# HB-UNI-SenAct-4-4-RC_V3_0.net
KiCad netlist of a schematic drawn in EAGLE
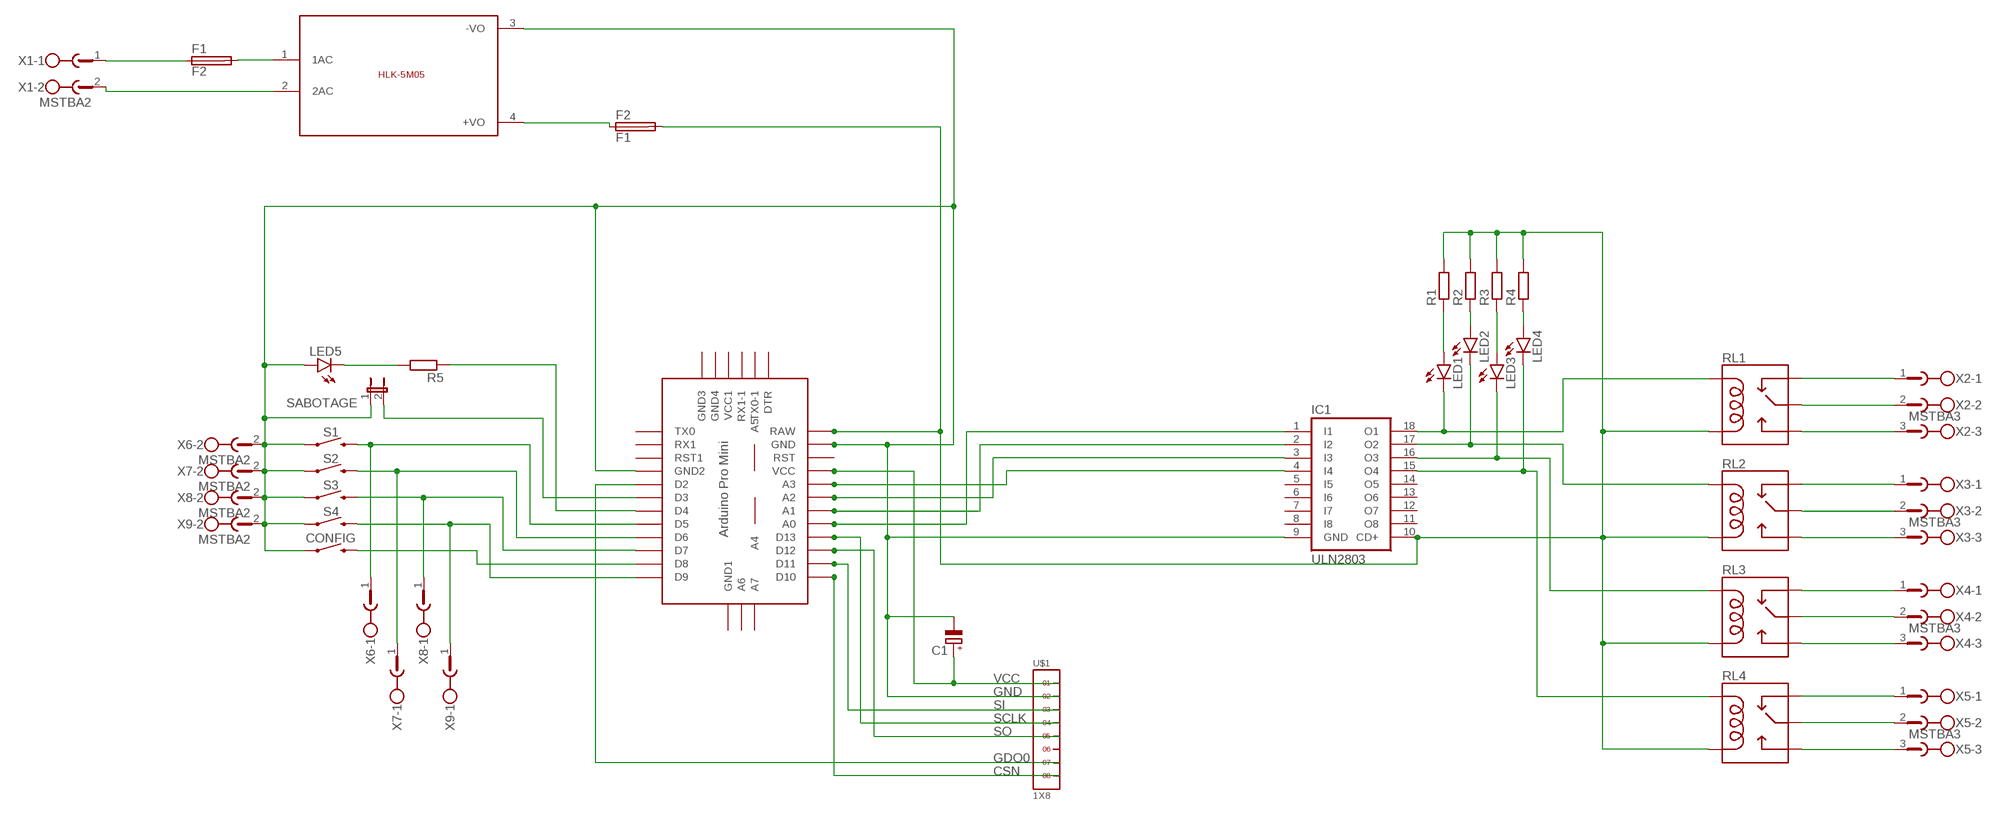
[diagram p0: schematic, sheet 1]

(export (version "E")
  (design (tool "Eeschema 10.0.6"))
  (components
    (comp (ref "C1")
      (value "CPOL-EUE2.5-5")
      (footprint "eagle-import:E2,5-5")
      (libsource (lib "eagle-import") (part "CPOL-EUE2.5-5"))
    )
    (comp (ref "CONFIG")
      (value "MOMENTARY-SWITCH-SPST-PTH-6.0MM-KIT")
      (footprint "eagle-import:TACTILE_SWITCH_PTH_6.0MM_KIT")
      (libsource (lib "eagle-import") (part "MOMENTARY-SWITCH-SPST-PTH-6.0MM-KIT"))
    )
    (comp (ref "F1")
      (value "F2")
      (footprint "eagle-import:SH22,5A")
      (fields (field (name "MPN") "0031.7701.11"))
      (libsource (lib "eagle-import") (part "SH22,5A"))
    )
    (comp (ref "F2")
      (value "F1")
      (footprint "eagle-import:SH22,5A")
      (fields (field (name "MPN") "0031.7701.11"))
      (libsource (lib "eagle-import") (part "SH22,5A"))
    )
    (comp (ref "IC1")
      (value "ULN2803")
      (footprint "eagle-import:DIL18")
      (libsource (lib "eagle-import") (part "ULN2803A"))
    )
    (comp (ref "LED1")
      (value "LED3MM")
      (footprint "eagle-import:LED3MM")
      (libsource (lib "eagle-import") (part "LED3MM"))
    )
    (comp (ref "LED2")
      (value "LED3MM")
      (footprint "eagle-import:LED3MM")
      (libsource (lib "eagle-import") (part "LED3MM"))
    )
    (comp (ref "LED3")
      (value "LED3MM")
      (footprint "eagle-import:LED3MM")
      (libsource (lib "eagle-import") (part "LED3MM"))
    )
    (comp (ref "LED4")
      (value "LED3MM")
      (footprint "eagle-import:LED3MM")
      (libsource (lib "eagle-import") (part "LED3MM"))
    )
    (comp (ref "LED5")
      (value "LED3MM")
      (footprint "eagle-import:LED3MM")
      (libsource (lib "eagle-import") (part "LED3MM"))
    )
    (comp (ref "R1")
      (value "R-EU_0309/10")
      (footprint "eagle-import:0309_10")
      (libsource (lib "eagle-import") (part "R-EU_0309/10"))
    )
    (comp (ref "R2")
      (value "R-EU_0309/10")
      (footprint "eagle-import:0309_10")
      (libsource (lib "eagle-import") (part "R-EU_0309/10"))
    )
    (comp (ref "R3")
      (value "R-EU_0309/10")
      (footprint "eagle-import:0309_10")
      (libsource (lib "eagle-import") (part "R-EU_0309/10"))
    )
    (comp (ref "R4")
      (value "R-EU_0309/10")
      (footprint "eagle-import:0309_10")
      (libsource (lib "eagle-import") (part "R-EU_0309/10"))
    )
    (comp (ref "R5")
      (value "R-EU_0309/10")
      (footprint "eagle-import:0309_10")
      (libsource (lib "eagle-import") (part "R-EU_0309/10"))
    )
    (comp (ref "RL1")
      (value "RELAYPTH")
      (footprint "eagle-import:SRD-05VDC-SL-C")
      (libsource (lib "eagle-import") (part "RELAYPTH"))
    )
    (comp (ref "RL2")
      (value "RL2")
      (footprint "eagle-import:SRD-05VDC-SL-C")
      (libsource (lib "eagle-import") (part "RELAYPTH"))
    )
    (comp (ref "RL3")
      (value "RELAYPTH")
      (footprint "eagle-import:SRD-05VDC-SL-C")
      (libsource (lib "eagle-import") (part "RELAYPTH"))
    )
    (comp (ref "RL4")
      (value "RELAYPTH")
      (footprint "eagle-import:SRD-05VDC-SL-C")
      (libsource (lib "eagle-import") (part "RELAYPTH"))
    )
    (comp (ref "S1")
      (value "MOMENTARY-SWITCH-SPST-PTH-6.0MM")
      (footprint "eagle-import:TACTILE_SWITCH_PTH_6.0MM")
      (libsource (lib "eagle-import") (part "MOMENTARY-SWITCH-SPST-PTH-6.0MM"))
    )
    (comp (ref "S2")
      (value "MOMENTARY-SWITCH-SPST-PTH-6.0MM-KIT")
      (footprint "eagle-import:TACTILE_SWITCH_PTH_6.0MM_KIT")
      (libsource (lib "eagle-import") (part "MOMENTARY-SWITCH-SPST-PTH-6.0MM-KIT"))
    )
    (comp (ref "S3")
      (value "MOMENTARY-SWITCH-SPST-PTH-6.0MM-KIT")
      (footprint "eagle-import:TACTILE_SWITCH_PTH_6.0MM_KIT")
      (libsource (lib "eagle-import") (part "MOMENTARY-SWITCH-SPST-PTH-6.0MM-KIT"))
    )
    (comp (ref "S4")
      (value "MOMENTARY-SWITCH-SPST-PTH-6.0MM-KIT")
      (footprint "eagle-import:TACTILE_SWITCH_PTH_6.0MM_KIT")
      (libsource (lib "eagle-import") (part "MOMENTARY-SWITCH-SPST-PTH-6.0MM-KIT"))
    )
    (comp (ref "SABOTAGE")
      (value "JP1E")
      (footprint "eagle-import:JP1")
      (libsource (lib "eagle-import") (part "JP1E"))
    )
    (comp (ref "U$1")
      (value "1X8")
      (footprint "eagle-import:1X8")
      (libsource (lib "eagle-import") (part "1X8"))
    )
    (comp (ref "U$2")
      (value "ABK-PRO-MINI")
      (footprint "eagle-import:ABK-PRO-MINI")
      (libsource (lib "eagle-import") (part "ABK-PRO-MINI"))
    )
    (comp (ref "U$3")
      (value "5VDC/5W")
      (footprint "eagle-import:HLK-5M05")
      (libsource (lib "eagle-import") (part "HLK-5M05"))
    )
    (comp (ref "X1")
      (value "MSTBA2")
      (footprint "eagle-import:MSTBA2")
      (fields (field (name "MF") "FARNELL") (field (name "MPN") "1757242"))
      (libsource (lib "eagle-import") (part "MSTBA2"))
    )
    (comp (ref "X2")
      (value "MSTBA3")
      (footprint "eagle-import:MSTBA3")
      (fields (field (name "MF") "FARNELL") (field (name "MPN") "1757255"))
      (libsource (lib "eagle-import") (part "MSTBA3"))
    )
    (comp (ref "X3")
      (value "MSTBA3")
      (footprint "eagle-import:MSTBA3")
      (fields (field (name "MF") "FARNELL") (field (name "MPN") "1757255"))
      (libsource (lib "eagle-import") (part "MSTBA3"))
    )
    (comp (ref "X4")
      (value "MSTBA3")
      (footprint "eagle-import:MSTBA3")
      (fields (field (name "MF") "FARNELL") (field (name "MPN") "1757255"))
      (libsource (lib "eagle-import") (part "MSTBA3"))
    )
    (comp (ref "X5")
      (value "MSTBA3")
      (footprint "eagle-import:MSTBA3")
      (fields (field (name "MF") "FARNELL") (field (name "MPN") "1757255"))
      (libsource (lib "eagle-import") (part "MSTBA3"))
    )
    (comp (ref "X6")
      (value "MSTBA2")
      (footprint "eagle-import:MSTBA2")
      (fields (field (name "MF") "FARNELL") (field (name "MPN") "1757242"))
      (libsource (lib "eagle-import") (part "MSTBA2"))
    )
    (comp (ref "X7")
      (value "MSTBA2")
      (footprint "eagle-import:MSTBA2")
      (fields (field (name "MF") "FARNELL") (field (name "MPN") "1757242"))
      (libsource (lib "eagle-import") (part "MSTBA2"))
    )
    (comp (ref "X8")
      (value "MSTBA2")
      (footprint "eagle-import:MSTBA2")
      (fields (field (name "MF") "FARNELL") (field (name "MPN") "1757242"))
      (libsource (lib "eagle-import") (part "MSTBA2"))
    )
    (comp (ref "X9")
      (value "MSTBA2")
      (footprint "eagle-import:MSTBA2")
      (fields (field (name "MF") "FARNELL") (field (name "MPN") "1757242"))
      (libsource (lib "eagle-import") (part "MSTBA2"))
    )
  )
  (nets
    (net (code "1") (name "/CSN") (class "Default")
      (node (ref "U$1") (pin "8") (pinfunction "8_8") (pintype "bidirectional"))
      (node (ref "U$2") (pin "D10") (pinfunction "D10_D10") (pintype "bidirectional"))
    )
    (net (code "2") (name "/GDO0") (class "Default")
      (node (ref "U$1") (pin "7") (pinfunction "7_7") (pintype "bidirectional"))
      (node (ref "U$2") (pin "D2") (pinfunction "D2_D2") (pintype "bidirectional"))
    )
    (net (code "3") (name "/GND") (class "Default")
      (node (ref "C1") (pin "-") (pinfunction "-_-") (pintype "passive"))
      (node (ref "CONFIG") (pin "1") (pinfunction "1_1") (pintype "passive"))
      (node (ref "IC1") (pin "9") (pinfunction "GND_9") (pintype "power_in"))
      (node (ref "LED5") (pin "A") (pinfunction "A_A") (pintype "passive"))
      (node (ref "S1") (pin "1") (pinfunction "1_1") (pintype "passive"))
      (node (ref "S2") (pin "1") (pinfunction "1_1") (pintype "passive"))
      (node (ref "S3") (pin "1") (pinfunction "1_1") (pintype "passive"))
      (node (ref "S4") (pin "1") (pinfunction "1_1") (pintype "passive"))
      (node (ref "SABOTAGE") (pin "1") (pinfunction "1_1") (pintype "passive"))
      (node (ref "U$1") (pin "2") (pinfunction "2_2") (pintype "bidirectional"))
      (node (ref "U$2") (pin "GND") (pinfunction "GND_GND") (pintype "bidirectional"))
      (node (ref "U$2") (pin "GND1") (pinfunction "GND2_GND1") (pintype "bidirectional"))
      (node (ref "U$3") (pin "3") (pinfunction "-VO_3") (pintype "bidirectional"))
      (node (ref "X6") (pin "2") (pinfunction "1_2") (pintype "passive"))
      (node (ref "X7") (pin "2") (pinfunction "1_2") (pintype "passive"))
      (node (ref "X8") (pin "2") (pinfunction "1_2") (pintype "passive"))
      (node (ref "X9") (pin "2") (pinfunction "1_2") (pintype "passive"))
    )
    (net (code "4") (name "/SCLK") (class "Default")
      (node (ref "U$1") (pin "4") (pinfunction "4_4") (pintype "bidirectional"))
      (node (ref "U$2") (pin "D13") (pinfunction "D13_D13") (pintype "bidirectional"))
    )
    (net (code "5") (name "/SI") (class "Default")
      (node (ref "U$1") (pin "3") (pinfunction "3_3") (pintype "bidirectional"))
      (node (ref "U$2") (pin "D11") (pinfunction "D11_D11") (pintype "bidirectional"))
    )
    (net (code "6") (name "/SO") (class "Default")
      (node (ref "U$1") (pin "5") (pinfunction "5_5") (pintype "bidirectional"))
      (node (ref "U$2") (pin "D12") (pinfunction "D12_D12") (pintype "bidirectional"))
    )
    (net (code "7") (name "/VCC") (class "Default")
      (node (ref "C1") (pin "+") (pinfunction "+_+") (pintype "passive"))
      (node (ref "U$1") (pin "1") (pinfunction "1_1") (pintype "bidirectional"))
      (node (ref "U$2") (pin "VCC") (pinfunction "VCC_VCC") (pintype "bidirectional"))
    )
    (net (code "8") (name "Net-(CONFIG-2)") (class "Default")
      (node (ref "CONFIG") (pin "3") (pinfunction "2_3") (pintype "passive"))
      (node (ref "U$2") (pin "D8") (pinfunction "D8_D8") (pintype "bidirectional"))
    )
    (net (code "9") (name "Net-(F1-Pad1)") (class "Default")
      (node (ref "F1") (pin "1") (pinfunction "1_1") (pintype "passive"))
      (node (ref "X1") (pin "1") (pinfunction "1_1") (pintype "passive"))
    )
    (net (code "10") (name "Net-(IC1-CD+)") (class "Default")
      (node (ref "F2") (pin "2") (pinfunction "2_2") (pintype "passive"))
      (node (ref "IC1") (pin "10") (pinfunction "CD+_10") (pintype "passive"))
      (node (ref "R1") (pin "2") (pinfunction "2_2") (pintype "passive"))
      (node (ref "R2") (pin "2") (pinfunction "2_2") (pintype "passive"))
      (node (ref "R3") (pin "2") (pinfunction "2_2") (pintype "passive"))
      (node (ref "R4") (pin "2") (pinfunction "2_2") (pintype "passive"))
      (node (ref "RL1") (pin "COIL0") (pinfunction "COIL0_COIL0") (pintype "bidirectional"))
      (node (ref "RL2") (pin "COIL0") (pinfunction "COIL0_COIL0") (pintype "bidirectional"))
      (node (ref "RL3") (pin "COIL0") (pinfunction "COIL0_COIL0") (pintype "bidirectional"))
      (node (ref "RL4") (pin "COIL0") (pinfunction "COIL0_COIL0") (pintype "bidirectional"))
      (node (ref "U$2") (pin "RAW") (pinfunction "RAW_RAW") (pintype "bidirectional"))
    )
    (net (code "11") (name "Net-(IC1-I1)") (class "Default")
      (node (ref "IC1") (pin "1") (pinfunction "I1_1") (pintype "input"))
      (node (ref "U$2") (pin "A0") (pinfunction "A0_A0") (pintype "bidirectional"))
    )
    (net (code "12") (name "Net-(IC1-I2)") (class "Default")
      (node (ref "IC1") (pin "2") (pinfunction "I2_2") (pintype "input"))
      (node (ref "U$2") (pin "A1") (pinfunction "A1_A1") (pintype "bidirectional"))
    )
    (net (code "13") (name "Net-(IC1-I3)") (class "Default")
      (node (ref "IC1") (pin "3") (pinfunction "I3_3") (pintype "input"))
      (node (ref "U$2") (pin "A2") (pinfunction "A2_A2") (pintype "bidirectional"))
    )
    (net (code "14") (name "Net-(IC1-I4)") (class "Default")
      (node (ref "IC1") (pin "4") (pinfunction "I4_4") (pintype "input"))
      (node (ref "U$2") (pin "A3") (pinfunction "A3_A3") (pintype "bidirectional"))
    )
    (net (code "15") (name "Net-(IC1-O1)") (class "Default")
      (node (ref "IC1") (pin "18") (pinfunction "O1_18") (pintype "open_collector"))
      (node (ref "LED1") (pin "K") (pinfunction "C_K") (pintype "passive"))
      (node (ref "RL1") (pin "COIL1") (pinfunction "COIL1_COIL1") (pintype "bidirectional"))
    )
    (net (code "16") (name "Net-(IC1-O2)") (class "Default")
      (node (ref "IC1") (pin "17") (pinfunction "O2_17") (pintype "open_collector"))
      (node (ref "LED2") (pin "K") (pinfunction "C_K") (pintype "passive"))
      (node (ref "RL2") (pin "COIL1") (pinfunction "COIL1_COIL1") (pintype "bidirectional"))
    )
    (net (code "17") (name "Net-(IC1-O3)") (class "Default")
      (node (ref "IC1") (pin "16") (pinfunction "O3_16") (pintype "open_collector"))
      (node (ref "LED3") (pin "K") (pinfunction "C_K") (pintype "passive"))
      (node (ref "RL3") (pin "COIL1") (pinfunction "COIL1_COIL1") (pintype "bidirectional"))
    )
    (net (code "18") (name "Net-(IC1-O4)") (class "Default")
      (node (ref "IC1") (pin "15") (pinfunction "O4_15") (pintype "open_collector"))
      (node (ref "LED4") (pin "K") (pinfunction "C_K") (pintype "passive"))
      (node (ref "RL4") (pin "COIL1") (pinfunction "COIL1_COIL1") (pintype "bidirectional"))
    )
    (net (code "19") (name "Net-(LED1-PadA)") (class "Default")
      (node (ref "LED1") (pin "A") (pinfunction "A_A") (pintype "passive"))
      (node (ref "R1") (pin "1") (pinfunction "1_1") (pintype "passive"))
    )
    (net (code "20") (name "Net-(LED2-PadA)") (class "Default")
      (node (ref "LED2") (pin "A") (pinfunction "A_A") (pintype "passive"))
      (node (ref "R2") (pin "1") (pinfunction "1_1") (pintype "passive"))
    )
    (net (code "21") (name "Net-(LED3-PadA)") (class "Default")
      (node (ref "LED3") (pin "A") (pinfunction "A_A") (pintype "passive"))
      (node (ref "R3") (pin "1") (pinfunction "1_1") (pintype "passive"))
    )
    (net (code "22") (name "Net-(LED4-PadA)") (class "Default")
      (node (ref "LED4") (pin "A") (pinfunction "A_A") (pintype "passive"))
      (node (ref "R4") (pin "1") (pinfunction "1_1") (pintype "passive"))
    )
    (net (code "23") (name "Net-(LED5-C)") (class "Default")
      (node (ref "LED5") (pin "K") (pinfunction "C_K") (pintype "passive"))
      (node (ref "R5") (pin "2") (pinfunction "2_2") (pintype "passive"))
    )
    (net (code "24") (name "Net-(R5-Pad1)") (class "Default")
      (node (ref "R5") (pin "1") (pinfunction "1_1") (pintype "passive"))
      (node (ref "U$2") (pin "D4") (pinfunction "D4_D4") (pintype "bidirectional"))
    )
    (net (code "25") (name "Net-(RL1-SWCLOSE)") (class "Default")
      (node (ref "RL1") (pin "SWCLOSED") (pinfunction "SWCLOSE_SWCLOSED") (pintype "bidirectional"))
      (node (ref "X2") (pin "1") (pinfunction "1_1") (pintype "passive"))
    )
    (net (code "26") (name "Net-(RL2-SWCLOSE)") (class "Default")
      (node (ref "RL2") (pin "SWCLOSED") (pinfunction "SWCLOSE_SWCLOSED") (pintype "bidirectional"))
      (node (ref "X3") (pin "1") (pinfunction "1_1") (pintype "passive"))
    )
    (net (code "27") (name "Net-(RL3-SWCLOSE)") (class "Default")
      (node (ref "RL3") (pin "SWCLOSED") (pinfunction "SWCLOSE_SWCLOSED") (pintype "bidirectional"))
      (node (ref "X4") (pin "1") (pinfunction "1_1") (pintype "passive"))
    )
    (net (code "28") (name "Net-(RL4-SWCLOSE)") (class "Default")
      (node (ref "RL4") (pin "SWCLOSED") (pinfunction "SWCLOSE_SWCLOSED") (pintype "bidirectional"))
      (node (ref "X5") (pin "1") (pinfunction "1_1") (pintype "passive"))
    )
    (net (code "29") (name "Net-(S1-2)") (class "Default")
      (node (ref "S1") (pin "3") (pinfunction "2_3") (pintype "passive"))
      (node (ref "U$2") (pin "D5") (pinfunction "D5_D5") (pintype "bidirectional"))
      (node (ref "X6") (pin "1") (pinfunction "1_1") (pintype "passive"))
    )
    (net (code "30") (name "Net-(S2-2)") (class "Default")
      (node (ref "S2") (pin "3") (pinfunction "2_3") (pintype "passive"))
      (node (ref "U$2") (pin "D6") (pinfunction "D6_D6") (pintype "bidirectional"))
      (node (ref "X7") (pin "1") (pinfunction "1_1") (pintype "passive"))
    )
    (net (code "31") (name "Net-(S3-2)") (class "Default")
      (node (ref "S3") (pin "3") (pinfunction "2_3") (pintype "passive"))
      (node (ref "U$2") (pin "D7") (pinfunction "D7_D7") (pintype "bidirectional"))
      (node (ref "X8") (pin "1") (pinfunction "1_1") (pintype "passive"))
    )
    (net (code "32") (name "Net-(S4-2)") (class "Default")
      (node (ref "S4") (pin "3") (pinfunction "2_3") (pintype "passive"))
      (node (ref "U$2") (pin "D9") (pinfunction "D9_D9") (pintype "bidirectional"))
      (node (ref "X9") (pin "1") (pinfunction "1_1") (pintype "passive"))
    )
    (net (code "33") (name "Net-(SABOTAGE-Pad2)") (class "Default")
      (node (ref "SABOTAGE") (pin "2") (pinfunction "2_2") (pintype "passive"))
      (node (ref "U$2") (pin "D3") (pinfunction "D3_D3") (pintype "bidirectional"))
    )
    (net (code "34") (name "Net-(U$3-+VO)") (class "Default")
      (node (ref "F2") (pin "1") (pinfunction "1_1") (pintype "passive"))
      (node (ref "U$3") (pin "4") (pinfunction "+VO_4") (pintype "bidirectional"))
    )
    (net (code "35") (name "Net-(U$3-1AC)") (class "Default")
      (node (ref "F1") (pin "2") (pinfunction "2_2") (pintype "passive"))
      (node (ref "U$3") (pin "1") (pinfunction "1AC_1") (pintype "bidirectional"))
    )
    (net (code "36") (name "Net-(U$3-2AC)") (class "Default")
      (node (ref "U$3") (pin "2") (pinfunction "2AC_2") (pintype "bidirectional"))
      (node (ref "X1") (pin "2") (pinfunction "1_2") (pintype "passive"))
    )
    (net (code "37") (name "Net-(X2B-1)") (class "Default")
      (node (ref "RL1") (pin "SWCOMMON") (pinfunction "SWCOMMON_SWCOMMON") (pintype "bidirectional"))
      (node (ref "X2") (pin "2") (pinfunction "1_2") (pintype "passive"))
    )
    (net (code "38") (name "Net-(X2C-1)") (class "Default")
      (node (ref "RL1") (pin "SWOPEN") (pinfunction "SWOPEN_SWOPEN") (pintype "bidirectional"))
      (node (ref "X2") (pin "3") (pinfunction "1_3") (pintype "passive"))
    )
    (net (code "39") (name "Net-(X3B-1)") (class "Default")
      (node (ref "RL2") (pin "SWCOMMON") (pinfunction "SWCOMMON_SWCOMMON") (pintype "bidirectional"))
      (node (ref "X3") (pin "2") (pinfunction "1_2") (pintype "passive"))
    )
    (net (code "40") (name "Net-(X3C-1)") (class "Default")
      (node (ref "RL2") (pin "SWOPEN") (pinfunction "SWOPEN_SWOPEN") (pintype "bidirectional"))
      (node (ref "X3") (pin "3") (pinfunction "1_3") (pintype "passive"))
    )
    (net (code "41") (name "Net-(X4B-1)") (class "Default")
      (node (ref "RL3") (pin "SWCOMMON") (pinfunction "SWCOMMON_SWCOMMON") (pintype "bidirectional"))
      (node (ref "X4") (pin "2") (pinfunction "1_2") (pintype "passive"))
    )
    (net (code "42") (name "Net-(X4C-1)") (class "Default")
      (node (ref "RL3") (pin "SWOPEN") (pinfunction "SWOPEN_SWOPEN") (pintype "bidirectional"))
      (node (ref "X4") (pin "3") (pinfunction "1_3") (pintype "passive"))
    )
    (net (code "43") (name "Net-(X5B-1)") (class "Default")
      (node (ref "RL4") (pin "SWCOMMON") (pinfunction "SWCOMMON_SWCOMMON") (pintype "bidirectional"))
      (node (ref "X5") (pin "2") (pinfunction "1_2") (pintype "passive"))
    )
    (net (code "44") (name "Net-(X5C-1)") (class "Default")
      (node (ref "RL4") (pin "SWOPEN") (pinfunction "SWOPEN_SWOPEN") (pintype "bidirectional"))
      (node (ref "X5") (pin "3") (pinfunction "1_3") (pintype "passive"))
    )
    (net (code "45") (name "unconnected-(IC1-I5-Pad5)") (class "Default")
      (node (ref "IC1") (pin "5") (pinfunction "I5_5") (pintype "input"))
    )
    (net (code "46") (name "unconnected-(IC1-I6-Pad6)") (class "Default")
      (node (ref "IC1") (pin "6") (pinfunction "I6_6") (pintype "input"))
    )
    (net (code "47") (name "unconnected-(IC1-I7-Pad7)") (class "Default")
      (node (ref "IC1") (pin "7") (pinfunction "I7_7") (pintype "input"))
    )
    (net (code "48") (name "unconnected-(IC1-I8-Pad8)") (class "Default")
      (node (ref "IC1") (pin "8") (pinfunction "I8_8") (pintype "input"))
    )
    (net (code "49") (name "unconnected-(IC1-O5-Pad14)") (class "Default")
      (node (ref "IC1") (pin "14") (pinfunction "O5_14") (pintype "open_collector"))
    )
    (net (code "50") (name "unconnected-(IC1-O6-Pad13)") (class "Default")
      (node (ref "IC1") (pin "13") (pinfunction "O6_13") (pintype "open_collector"))
    )
    (net (code "51") (name "unconnected-(IC1-O7-Pad12)") (class "Default")
      (node (ref "IC1") (pin "12") (pinfunction "O7_12") (pintype "open_collector"))
    )
    (net (code "52") (name "unconnected-(IC1-O8-Pad11)") (class "Default")
      (node (ref "IC1") (pin "11") (pinfunction "O8_11") (pintype "open_collector"))
    )
    (net (code "53") (name "unconnected-(U$1-Pad6)") (class "Default")
      (node (ref "U$1") (pin "6") (pinfunction "6_6") (pintype "bidirectional"))
    )
    (net (code "54") (name "unconnected-(U$2-GND1-PadGND4)") (class "Default")
      (node (ref "U$2") (pin "GND4") (pinfunction "GND1_GND4") (pintype "bidirectional"))
    )
    (net (code "55") (name "unconnected-(U$2-GND3-PadGND2)") (class "Default")
      (node (ref "U$2") (pin "GND2") (pinfunction "GND3_GND2") (pintype "bidirectional"))
    )
    (net (code "56") (name "unconnected-(U$2-GND4-PadGND3)") (class "Default")
      (node (ref "U$2") (pin "GND3") (pinfunction "GND4_GND3") (pintype "bidirectional"))
    )
    (net (code "57") (name "unconnected-(U$2-PadA4)") (class "Default")
      (node (ref "U$2") (pin "A4") (pinfunction "A4_A4") (pintype "bidirectional"))
    )
    (net (code "58") (name "unconnected-(U$2-PadA5)") (class "Default")
      (node (ref "U$2") (pin "A5") (pinfunction "A5_A5") (pintype "bidirectional"))
    )
    (net (code "59") (name "unconnected-(U$2-PadA6)") (class "Default")
      (node (ref "U$2") (pin "A6") (pinfunction "A6_A6") (pintype "bidirectional"))
    )
    (net (code "60") (name "unconnected-(U$2-PadA7)") (class "Default")
      (node (ref "U$2") (pin "A7") (pinfunction "A7_A7") (pintype "bidirectional"))
    )
    (net (code "61") (name "unconnected-(U$2-PadDTR)") (class "Default")
      (node (ref "U$2") (pin "DTR") (pinfunction "DTR_DTR") (pintype "bidirectional"))
    )
    (net (code "62") (name "unconnected-(U$2-PadRST)") (class "Default")
      (node (ref "U$2") (pin "RST") (pinfunction "RST_RST") (pintype "bidirectional"))
    )
    (net (code "63") (name "unconnected-(U$2-PadRST1)") (class "Default")
      (node (ref "U$2") (pin "RST1") (pinfunction "RST1_RST1") (pintype "bidirectional"))
    )
    (net (code "64") (name "unconnected-(U$2-PadRX1)") (class "Default")
      (node (ref "U$2") (pin "RX1") (pinfunction "RX1_RX1") (pintype "bidirectional"))
    )
    (net (code "65") (name "unconnected-(U$2-PadRX1-1)") (class "Default")
      (node (ref "U$2") (pin "RX1-1") (pinfunction "RX1-1_RX1-1") (pintype "bidirectional"))
    )
    (net (code "66") (name "unconnected-(U$2-PadTX0)") (class "Default")
      (node (ref "U$2") (pin "TX0") (pinfunction "TX0_TX0") (pintype "bidirectional"))
    )
    (net (code "67") (name "unconnected-(U$2-PadTX0-1)") (class "Default")
      (node (ref "U$2") (pin "TX0-1") (pinfunction "TX0-1_TX0-1") (pintype "bidirectional"))
    )
    (net (code "68") (name "unconnected-(U$2-PadVCC1)") (class "Default")
      (node (ref "U$2") (pin "VCC1") (pinfunction "VCC1_VCC1") (pintype "bidirectional"))
    )
  )
)
